# STM32G4_microcontroller.net
KiCad netlist of a schematic drawn in Altium Designer
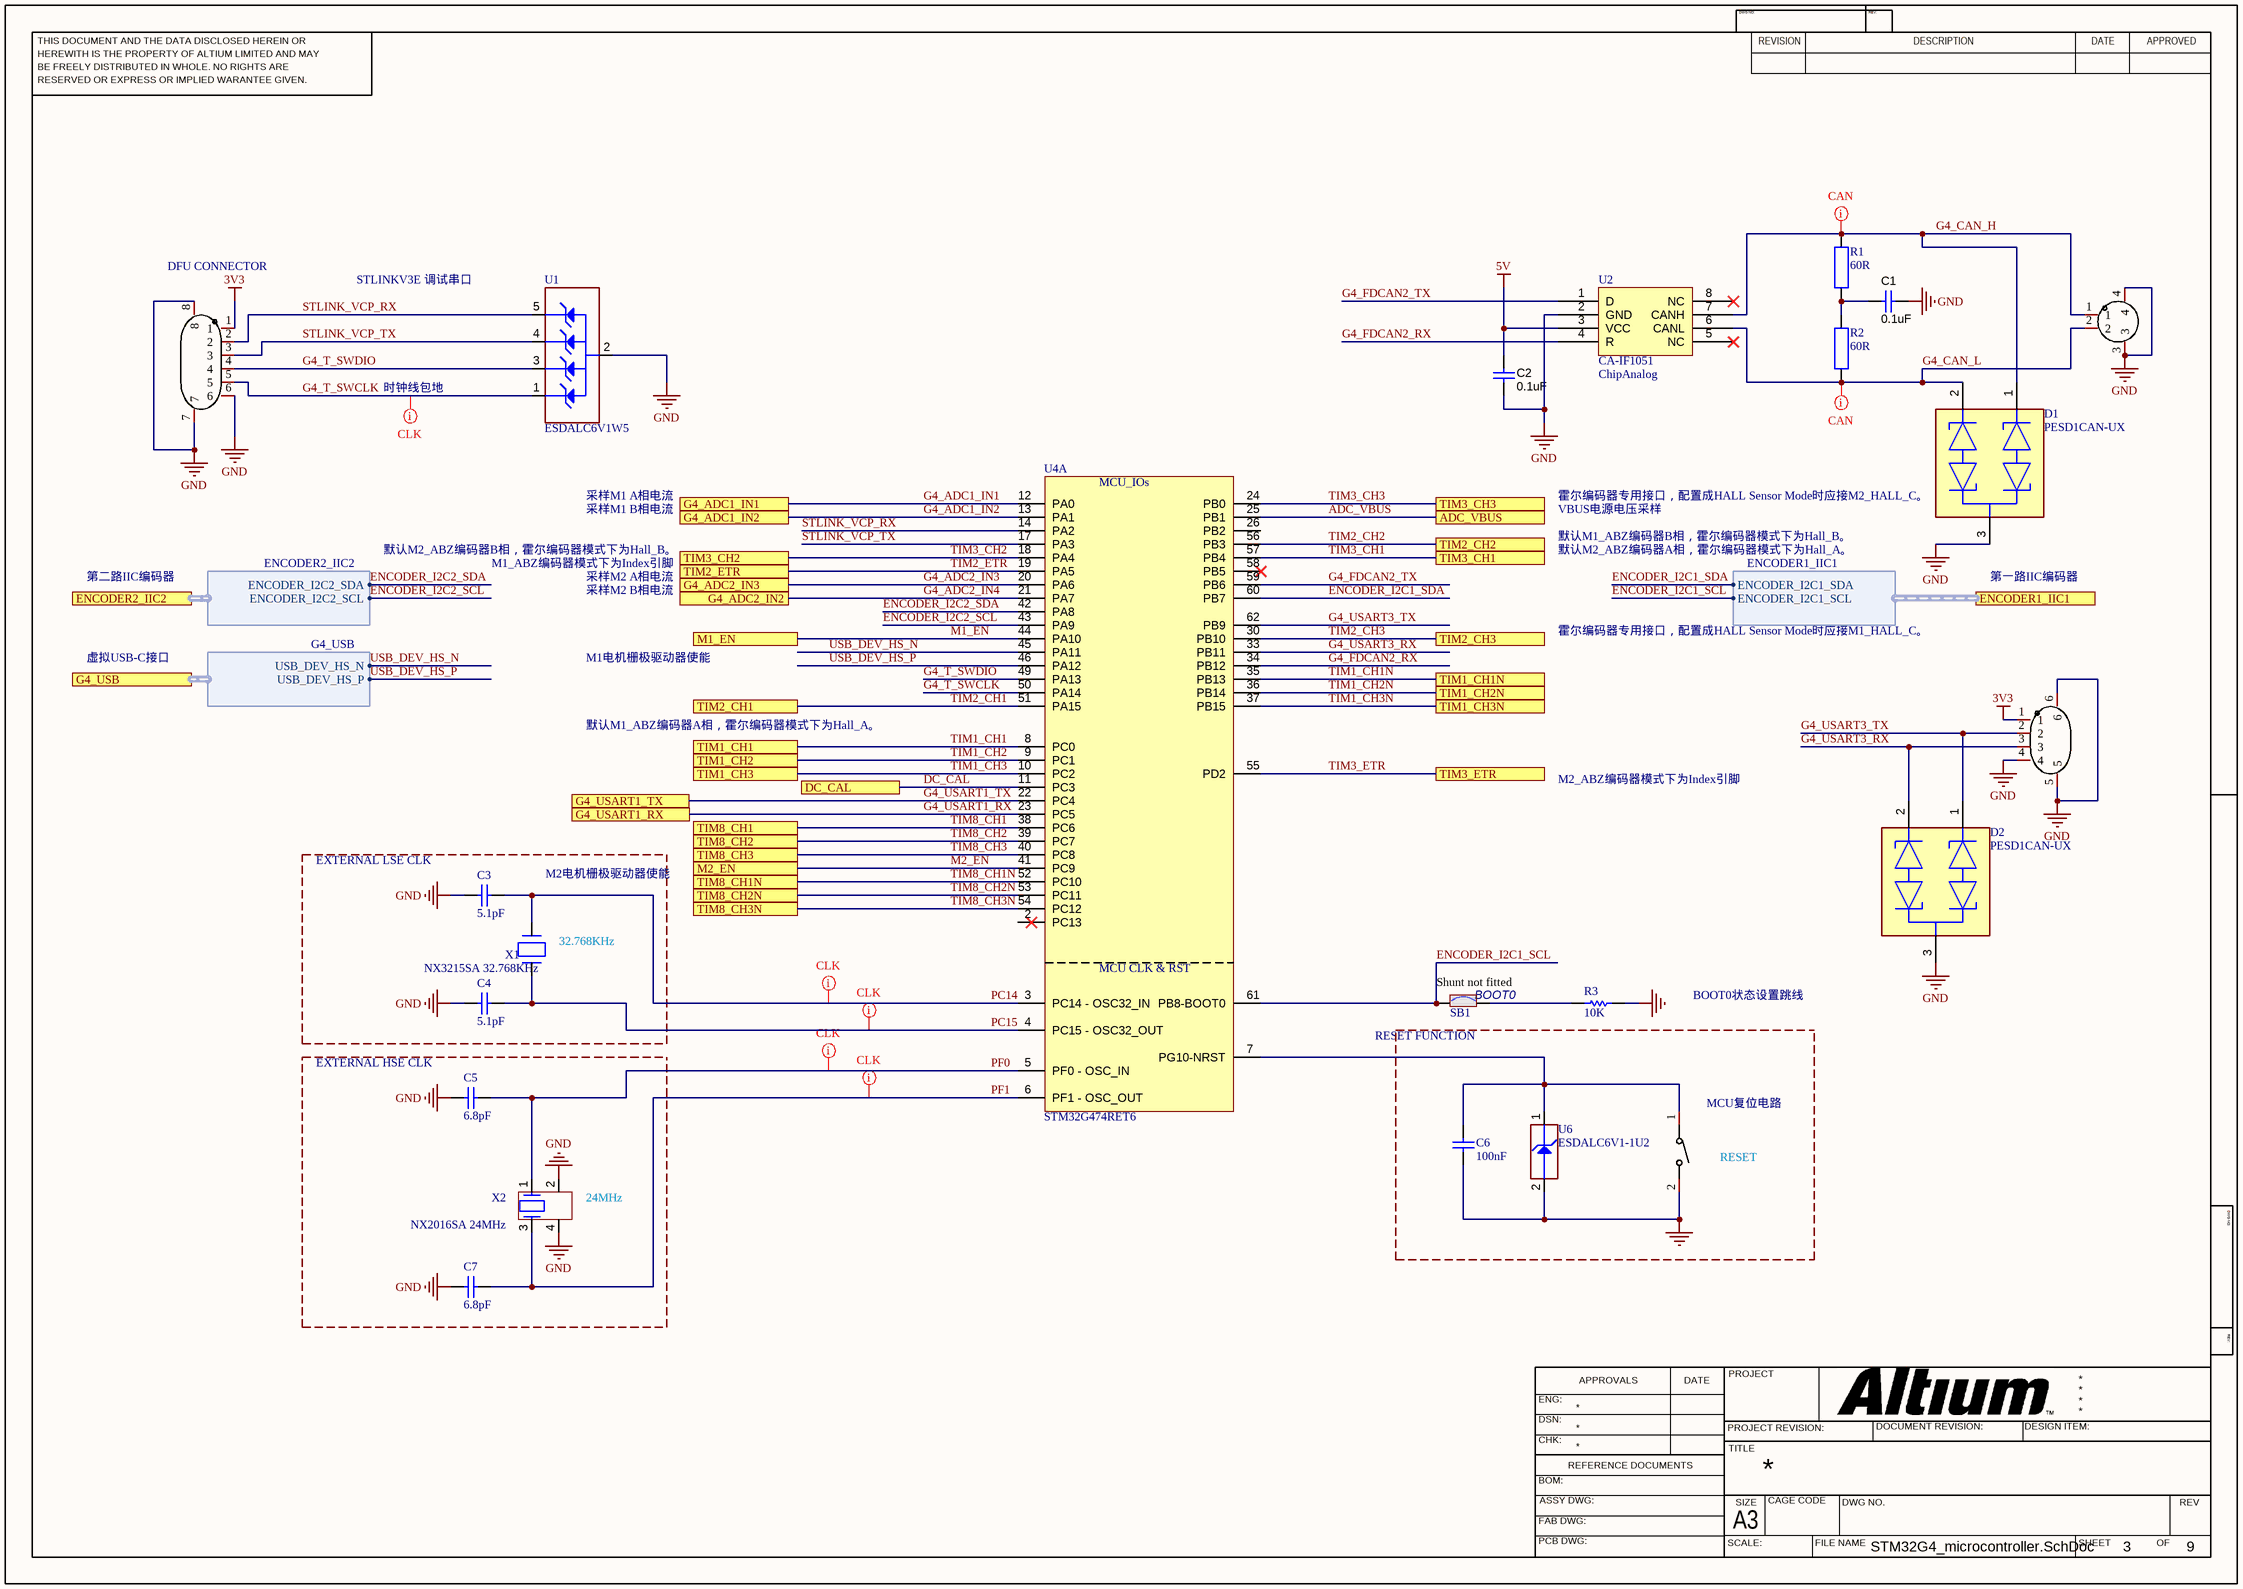
[diagram p0: STM32G4_microcontroller.SchDoc]

(export (version "E")
  (design (tool "Eeschema 10.0.6"))
  (components
    (comp (ref "C1")
      (value "GRM188R61E105KA12D")
      (footprint "0603L")
      (description "CAP, CERM, 0.1uF, 25V, +/-10%, X5R, 0603")
      (fields
        (field (name "VALUEDISPLAYED") "0.1uF")
        (field (name "MANUFACTURER") "MuRata")
        (field (name "PUBLISHER") "Texas Instruments")
      )
      (libsource (lib "Capacitor_Ceramic") (part "GRM188R61E105KA12D"))
    )
    (comp (ref "C2")
      (value "GRM188R61E105KA12D")
      (footprint "0603L")
      (description "CAP, CERM, 0.1uF, 25V, +/-10%, X5R, 0603")
      (fields
        (field (name "VALUEDISPLAYED") "0.1uF")
        (field (name "MANUFACTURER") "MuRata")
        (field (name "PUBLISHER") "Texas Instruments")
      )
      (libsource (lib "Capacitor_Ceramic") (part "GRM188R61E105KA12D"))
    )
    (comp (ref "C3")
      (value "5.1pF")
      (footprint "C0402")
      (description "Capacitor, MLCC, 5.1pF, 50V, NPO, +-0.25pF, 0402, T=0.5mm")
      (fields
        (field (name "INTERNAL_PART_NUMBER") "MCD-00003")
        (field (name "MANUFACTURER_PART_NUMBER") "CC0402CRNPO9BN5R1")
        (field (name "PROVIDED_BY") "SUBCO")
      )
      (libsource (lib "MCD_PARTS_database") (part "Capacitor"))
    )
    (comp (ref "C4")
      (value "5.1pF")
      (footprint "C0402")
      (description "Capacitor, MLCC, 5.1pF, 50V, NPO, +-0.25pF, 0402, T=0.5mm")
      (fields
        (field (name "INTERNAL_PART_NUMBER") "MCD-00003")
        (field (name "MANUFACTURER_PART_NUMBER") "CC0402CRNPO9BN5R1")
        (field (name "PROVIDED_BY") "SUBCO")
      )
      (libsource (lib "MCD_PARTS_database") (part "Capacitor"))
    )
    (comp (ref "C5")
      (value "6.8pF")
      (footprint "C0402")
      (description "Capacitor, MLCC, 6.8pF, 50V, NPO, +-0.25pF, 0402, T=0.5mm")
      (fields
        (field (name "INTERNAL_PART_NUMBER") "MCD-00674")
        (field (name "MANUFACTURER_PART_NUMBER") "CC0402CRNPO9BN6R8")
        (field (name "PROVIDED_BY") "SUBCO")
      )
      (libsource (lib "MCD_PARTS_database") (part "Capacitor"))
    )
    (comp (ref "C6")
      (value "100nF")
      (footprint "C0402")
      (description "Capacitor, MLCC, 100nF, 16V, X7R, 10%, 0402, T=0,5mm")
      (fields
        (field (name "INTERNAL_PART_NUMBER") "MCD-00102")
        (field (name "MANUFACTURER_PART_NUMBER") "CC0402KRX7R7BB104")
        (field (name "PROVIDED_BY") "Subcon")
      )
      (libsource (lib "MCD_PARTS_database") (part "Capacitor"))
    )
    (comp (ref "C7")
      (value "6.8pF")
      (footprint "C0402")
      (description "Capacitor, MLCC, 6.8pF, 50V, NPO, +-0.25pF, 0402, T=0.5mm")
      (fields
        (field (name "INTERNAL_PART_NUMBER") "MCD-00674")
        (field (name "MANUFACTURER_PART_NUMBER") "CC0402CRNPO9BN6R8")
        (field (name "PROVIDED_BY") "SUBCO")
      )
      (libsource (lib "MCD_PARTS_database") (part "Capacitor"))
    )
    (comp (ref "CN1")
      (value "WAFER-GH1.25-2PWB")
      (footprint "CONN-TH_2P-P1.25_XUNPU_WAFER-GH1.25-2PWB")
      (fields (field (name "MANUFACTURER") "XUNPU(讯普)"))
      (libsource (lib "two_ax_PCB") (part "WAFER-GH1.25-2PWB"))
    )
    (comp (ref "D1")
      (value "PESD1CAN-UX")
      (footprint "FP-SOT323-MFG")
      (description "TVS DIODE 24V 50V SC70-3")
      (libsource (lib "Altium Content Vault") (part "04d57993b6b7b0f5b3c95ba4f97dea0"))
    )
    (comp (ref "D2")
      (value "PESD1CAN-UX")
      (footprint "FP-SOT323-MFG")
      (description "TVS DIODE 24V 50V SC70-3")
      (libsource (lib "Altium Content Vault") (part "04d57993b6b7b0f5b3c95ba4f97dea0"))
    )
    (comp (ref "R1")
      (value "60R")
      (footprint "RESC1608X55N")
      (description "RES SMD 60 OHM 1% 1/10W 0603")
      (fields
        (field (name "MANUFACTURER") "Yageo")
        (field (name "MANUFACTURER PART NUMBER") "RC0603FR-07120RL")
      )
      (libsource (lib "CustomComponents") (part "RC0603FR-07120RL"))
    )
    (comp (ref "R2")
      (value "60R")
      (footprint "RESC1608X55N")
      (description "RES SMD 60 OHM 1% 1/10W 0603")
      (fields
        (field (name "MANUFACTURER") "Yageo")
        (field (name "MANUFACTURER PART NUMBER") "RC0603FR-07120RL")
      )
      (libsource (lib "CustomComponents") (part "RC0603FR-07120RL"))
    )
    (comp (ref "R3")
      (value "10K")
      (footprint "R0603")
      (description "Resistor,10K,0603,1%,1/10W")
      (fields
        (field (name "INTERNAL_PART_NUMBER") "MCD-00220")
        (field (name "MANUFACTURER_PART_NUMBER") "RC0603FR-0710KL")
        (field (name "PROVIDED_BY") "Subcon")
      )
      (libsource (lib "MCD_PARTS_database") (part "Resistor"))
    )
    (comp (ref "SB1")
      (value "MCD-00071")
      (footprint "SOLDER-BRIDGE_R0603-0R")
      (description "Solder Bridge ON")
      (fields
        (field (name "MANUFACTURER_PART_NUMBER") "RC0603JR-070RL")
        (field (name "MANUFACTURER") "YAGEO")
        (field (name "PROVIDED_BY") "SUBCO")
      )
      (libsource (lib "mb1367") (part "MCD-00071"))
    )
    (comp (ref "SW1")
      (value "TS-1088-AR02016")
      (footprint "SW-SMD_L3.9-W3.0-P4.45")
      (fields (field (name "MANUFACTURER") "XUNPU(讯普)"))
      (libsource (lib "mb1367") (part "TS-1088-AR02016"))
    )
    (comp (ref "U1")
      (value "ESDALC6V1W5")
      (footprint "ESD_SOT323-5L")
      (description "Dual Transil array for ESD protection")
      (fields
        (field (name "INTERNAL_PART_NUMBER") "MCD-00136")
        (field (name "MANUFACTURER") "STMICROELECTRONICS")
        (field (name "PROVIDED_BY") "Subcon")
      )
      (libsource (lib "MCD_PARTS_database") (part "ESDALC6V1W5"))
    )
    (comp (ref "U2")
      (value "CA-IF1051")
      (footprint "SOIC127P600X175-8N")
      (fields
        (field (name "MANUFACTURER") "Texas Instruments")
        (field (name "MANUFACTURER PART NUMBER") "CA-IF1051")
      )
      (libsource (lib "CustomComponents") (part "SN65HVD232D"))
    )
    (comp (ref "U3")
      (value "WAFER-GH1.25-6PWB")
      (footprint "CONN-SMD_6P-P1.25_XUNPU_WAFER-GH1.25-6PWB")
      (fields (field (name "MANUFACTURER") "XUNPU(讯普)"))
      (libsource (lib "two_ax_PCB") (part "WAFER-GH1.25-6PWB"))
    )
    (comp (ref "U4")
      (value "STM32G474RET6")
      (footprint "ICC_LQFP64_10X10_P050_SOCKET_YAMAICHI_IC149-064-069-B5_NM")
      (description "STM32G474, LQFP64 package,  3D IC footprint with 2D socket footprint.")
      (fields
        (field (name "INTERNAL_PART_NUMBER") "MCD-01243")
        (field (name "MANUFACTURER") "STMICROELECTRONICS")
        (field (name "PROVIDED_BY") "SUBCO with ST control")
      )
      (libsource (lib "MCD_PARTS_database") (part "STM32G4xx_LQFP64"))
    )
    (comp (ref "U5")
      (value "WAFER-GH1.25-4PWB")
      (footprint "CONN-SMD_4P-P1.25_XUNPU_WAFER-GH1.25-4PWB")
      (fields (field (name "MANUFACTURER") "XUNPU(讯普)"))
      (libsource (lib "two_ax_PCB") (part "WAFER-GH1.25-4PWB"))
    )
    (comp (ref "U6")
      (value "ESDALC6V1-1U2")
      (footprint "ESD_ST0201")
      (description "ESD protection 6V1")
      (fields
        (field (name "INTERNAL_PART_NUMBER") "MCD-00170")
        (field (name "MANUFACTURER") "STMICROELECTRONICS")
        (field (name "PROVIDED_BY") "Subcon")
      )
      (libsource (lib "MCD_PARTS_database") (part "ESD-TRANSIL"))
    )
    (comp (ref "X1")
      (value "NX3215SA 32.768KHz")
      (footprint "CRY_NX3215SA_2P")
      (description "Crystal 32.768kHz, 6pF, +-20ppm, 50Kohms max, SMD")
      (fields
        (field (name "INTERNAL_PART_NUMBER") "MCD-00091")
        (field (name "MANUFACTURER_PART_NUMBER") "NX3215SA 32.768KHz EXS00A-MU00525")
        (field (name "PROVIDED_BY") "SUBCO")
      )
      (libsource (lib "MCD_PARTS_database") (part "XTAL_2_PINS"))
    )
    (comp (ref "X2")
      (value "NX2016SA 24MHz")
      (footprint "CRY_NX2016SA_4P")
      (description "Crystal 24MHz, 6pF, +-20ppm, 80ohms max, SMD")
      (fields
        (field (name "INTERNAL_PART_NUMBER") "MCD-01036")
        (field (name "MANUFACTURER_PART_NUMBER") "NX2016SA 24MHz EXS00A-CS10820")
        (field (name "PROVIDED_BY") "SUBCO")
      )
      (libsource (lib "MCD_PARTS_database") (part "XTAL_4_PINS"))
    )
  )
  (nets
    (net (code "4") (name "/ADC_VBUS") (class "Default")
      (node (ref "U4") (pin "25") (pinfunction "PB1_25") (pintype "passive"))
    )
    (net (code "5") (name "/DC_CAL") (class "Default")
      (node (ref "U4") (pin "11") (pinfunction "PC3_11") (pintype "passive"))
    )
    (net (code "6") (name "/ENCODER_I2C1_SCL") (class "Default")
      (node (ref "SB1") (pin "1") (pinfunction "1_1") (pintype "passive"))
      (node (ref "U4") (pin "61") (pinfunction "PB8-BOOT0_61") (pintype "passive"))
    )
    (net (code "7") (name "/ENCODER_I2C1_SDA") (class "Default")
      (node (ref "U4") (pin "60") (pinfunction "PB7_60") (pintype "passive"))
    )
    (net (code "8") (name "/ENCODER_I2C2_SCL") (class "Default")
      (node (ref "U4") (pin "43") (pinfunction "PA9_43") (pintype "passive"))
    )
    (net (code "9") (name "/ENCODER_I2C2_SDA") (class "Default")
      (node (ref "U4") (pin "42") (pinfunction "PA8_42") (pintype "passive"))
    )
    (net (code "10") (name "/G4_ADC1_IN1") (class "Default")
      (node (ref "U4") (pin "12") (pinfunction "PA0_12") (pintype "passive"))
    )
    (net (code "11") (name "/G4_ADC1_IN2") (class "Default")
      (node (ref "U4") (pin "13") (pinfunction "PA1_13") (pintype "passive"))
    )
    (net (code "12") (name "/G4_ADC2_IN3") (class "Default")
      (node (ref "U4") (pin "20") (pinfunction "PA6_20") (pintype "passive"))
    )
    (net (code "13") (name "/G4_ADC2_IN4") (class "Default")
      (node (ref "U4") (pin "21") (pinfunction "PA7_21") (pintype "passive"))
    )
    (net (code "14") (name "/G4_CAN_H") (class "Default")
      (node (ref "CN1") (pin "1") (pinfunction "1_1") (pintype "passive"))
      (node (ref "D1") (pin "1") (pinfunction "cathode_1_1") (pintype "passive"))
      (node (ref "R1") (pin "2") (pinfunction "0_2") (pintype "passive"))
      (node (ref "U2") (pin "7") (pinfunction "CANH_7") (pintype "passive"))
    )
    (net (code "15") (name "/G4_CAN_L") (class "Default")
      (node (ref "CN1") (pin "2") (pinfunction "2_2") (pintype "passive"))
      (node (ref "D1") (pin "2") (pinfunction "cathode_2_2") (pintype "passive"))
      (node (ref "R2") (pin "1") (pinfunction "0_1") (pintype "passive"))
      (node (ref "U2") (pin "6") (pinfunction "CANL_6") (pintype "passive"))
    )
    (net (code "16") (name "/G4_FDCAN2_RX") (class "Default")
      (node (ref "U2") (pin "4") (pinfunction "R_4") (pintype "passive"))
      (node (ref "U4") (pin "34") (pinfunction "PB12_34") (pintype "passive"))
    )
    (net (code "17") (name "/G4_FDCAN2_TX") (class "Default")
      (node (ref "U2") (pin "1") (pinfunction "D_1") (pintype "passive"))
      (node (ref "U4") (pin "59") (pinfunction "PB6_59") (pintype "passive"))
    )
    (net (code "18") (name "/G4_T_SWCLK") (class "Default")
      (node (ref "U1") (pin "1") (pinfunction "IO1_1") (pintype "passive"))
      (node (ref "U3") (pin "5") (pinfunction "5_5") (pintype "passive"))
      (node (ref "U4") (pin "50") (pinfunction "PA14_50") (pintype "passive"))
    )
    (net (code "19") (name "/G4_T_SWDIO") (class "Default")
      (node (ref "U1") (pin "3") (pinfunction "IO2_3") (pintype "passive"))
      (node (ref "U3") (pin "4") (pinfunction "4_4") (pintype "passive"))
      (node (ref "U4") (pin "49") (pinfunction "PA13_49") (pintype "passive"))
    )
    (net (code "20") (name "/G4_USART1_RX") (class "Default")
      (node (ref "U4") (pin "23") (pinfunction "PC5_23") (pintype "passive"))
    )
    (net (code "21") (name "/G4_USART1_TX") (class "Default")
      (node (ref "U4") (pin "22") (pinfunction "PC4_22") (pintype "passive"))
    )
    (net (code "22") (name "/G4_USART3_RX") (class "Default")
      (node (ref "D2") (pin "2") (pinfunction "cathode_2_2") (pintype "passive"))
      (node (ref "U4") (pin "33") (pinfunction "PB11_33") (pintype "passive"))
      (node (ref "U5") (pin "3") (pinfunction "3_3") (pintype "passive"))
    )
    (net (code "23") (name "/G4_USART3_TX") (class "Default")
      (node (ref "D2") (pin "1") (pinfunction "cathode_1_1") (pintype "passive"))
      (node (ref "U4") (pin "62") (pinfunction "PB9_62") (pintype "passive"))
      (node (ref "U5") (pin "2") (pinfunction "2_2") (pintype "passive"))
    )
    (net (code "24") (name "/M1_EN") (class "Default")
      (node (ref "U4") (pin "44") (pinfunction "PA10_44") (pintype "passive"))
    )
    (net (code "25") (name "/M2_EN") (class "Default")
      (node (ref "U4") (pin "41") (pinfunction "PC9_41") (pintype "passive"))
    )
    (net (code "26") (name "/PC14") (class "Default")
      (node (ref "C3") (pin "1") (pinfunction "1_1") (pintype "passive"))
      (node (ref "U4") (pin "3") (pinfunction "PC14_-_OSC32_IN_3") (pintype "passive"))
      (node (ref "X1") (pin "2") (pinfunction "X2_2") (pintype "passive"))
    )
    (net (code "27") (name "/PC15") (class "Default")
      (node (ref "C4") (pin "1") (pinfunction "1_1") (pintype "passive"))
      (node (ref "U4") (pin "4") (pinfunction "PC15_-_OSC32_OUT_4") (pintype "passive"))
      (node (ref "X1") (pin "1") (pinfunction "X1_1") (pintype "passive"))
    )
    (net (code "28") (name "/PF0") (class "Default")
      (node (ref "C5") (pin "2") (pinfunction "2_2") (pintype "passive"))
      (node (ref "U4") (pin "5") (pinfunction "PF0_-_OSC_IN_5") (pintype "passive"))
      (node (ref "X2") (pin "1") (pinfunction "1_1") (pintype "passive"))
    )
    (net (code "29") (name "/PF1") (class "Default")
      (node (ref "C7") (pin "2") (pinfunction "2_2") (pintype "passive"))
      (node (ref "U4") (pin "6") (pinfunction "PF1_-_OSC_OUT_6") (pintype "passive"))
      (node (ref "X2") (pin "3") (pinfunction "3_3") (pintype "passive"))
    )
    (net (code "30") (name "/STLINK_VCP_RX") (class "Default")
      (node (ref "U1") (pin "5") (pinfunction "IO4_5") (pintype "passive"))
      (node (ref "U3") (pin "2") (pinfunction "2_2") (pintype "passive"))
      (node (ref "U4") (pin "14") (pinfunction "PA2_14") (pintype "passive"))
    )
    (net (code "31") (name "/STLINK_VCP_TX") (class "Default")
      (node (ref "U1") (pin "4") (pinfunction "IO3_4") (pintype "passive"))
      (node (ref "U3") (pin "3") (pinfunction "3_3") (pintype "passive"))
      (node (ref "U4") (pin "17") (pinfunction "PA3_17") (pintype "passive"))
    )
    (net (code "32") (name "/TIM1_CH1") (class "Default")
      (node (ref "U4") (pin "8") (pinfunction "PC0_8") (pintype "passive"))
    )
    (net (code "33") (name "/TIM1_CH1N") (class "Default")
      (node (ref "U4") (pin "35") (pinfunction "PB13_35") (pintype "passive"))
    )
    (net (code "34") (name "/TIM1_CH2") (class "Default")
      (node (ref "U4") (pin "9") (pinfunction "PC1_9") (pintype "passive"))
    )
    (net (code "35") (name "/TIM1_CH2N") (class "Default")
      (node (ref "U4") (pin "36") (pinfunction "PB14_36") (pintype "passive"))
    )
    (net (code "36") (name "/TIM1_CH3") (class "Default")
      (node (ref "U4") (pin "10") (pinfunction "PC2_10") (pintype "passive"))
    )
    (net (code "37") (name "/TIM1_CH3N") (class "Default")
      (node (ref "U4") (pin "37") (pinfunction "PB15_37") (pintype "passive"))
    )
    (net (code "38") (name "/TIM2_CH1") (class "Default")
      (node (ref "U4") (pin "51") (pinfunction "PA15_51") (pintype "passive"))
    )
    (net (code "39") (name "/TIM2_CH2") (class "Default")
      (node (ref "U4") (pin "56") (pinfunction "PB3_56") (pintype "passive"))
    )
    (net (code "40") (name "/TIM2_CH3") (class "Default")
      (node (ref "U4") (pin "30") (pinfunction "PB10_30") (pintype "passive"))
    )
    (net (code "41") (name "/TIM2_ETR") (class "Default")
      (node (ref "U4") (pin "19") (pinfunction "PA5_19") (pintype "passive"))
    )
    (net (code "42") (name "/TIM3_CH1") (class "Default")
      (node (ref "U4") (pin "57") (pinfunction "PB4_57") (pintype "passive"))
    )
    (net (code "43") (name "/TIM3_CH2") (class "Default")
      (node (ref "U4") (pin "18") (pinfunction "PA4_18") (pintype "passive"))
    )
    (net (code "44") (name "/TIM3_CH3") (class "Default")
      (node (ref "U4") (pin "24") (pinfunction "PB0_24") (pintype "passive"))
    )
    (net (code "45") (name "/TIM3_ETR") (class "Default")
      (node (ref "U4") (pin "55") (pinfunction "PD2_55") (pintype "passive"))
    )
    (net (code "46") (name "/TIM8_CH1") (class "Default")
      (node (ref "U4") (pin "38") (pinfunction "PC6_38") (pintype "passive"))
    )
    (net (code "47") (name "/TIM8_CH1N") (class "Default")
      (node (ref "U4") (pin "52") (pinfunction "PC10_52") (pintype "passive"))
    )
    (net (code "48") (name "/TIM8_CH2") (class "Default")
      (node (ref "U4") (pin "39") (pinfunction "PC7_39") (pintype "passive"))
    )
    (net (code "49") (name "/TIM8_CH2N") (class "Default")
      (node (ref "U4") (pin "53") (pinfunction "PC11_53") (pintype "passive"))
    )
    (net (code "50") (name "/TIM8_CH3") (class "Default")
      (node (ref "U4") (pin "40") (pinfunction "PC8_40") (pintype "passive"))
    )
    (net (code "51") (name "/TIM8_CH3N") (class "Default")
      (node (ref "U4") (pin "54") (pinfunction "PC12_54") (pintype "passive"))
    )
    (net (code "52") (name "/USB_DEV_HS_N") (class "Default")
      (node (ref "U4") (pin "45") (pinfunction "PA11_45") (pintype "passive"))
    )
    (net (code "53") (name "/USB_DEV_HS_P") (class "Default")
      (node (ref "U4") (pin "46") (pinfunction "PA12_46") (pintype "passive"))
    )
    (net (code "57") (name "3V3") (class "Default")
      (node (ref "U3") (pin "1") (pinfunction "1_1") (pintype "passive"))
      (node (ref "U5") (pin "1") (pinfunction "1_1") (pintype "passive"))
    )
    (net (code "58") (name "5V") (class "Default")
      (node (ref "C2") (pin "1") (pinfunction "1_1") (pintype "passive"))
      (node (ref "U2") (pin "3") (pinfunction "VCC_3") (pintype "passive"))
    )
    (net (code "59") (name "GND") (class "Default")
      (node (ref "C1") (pin "2") (pinfunction "2_2") (pintype "passive"))
      (node (ref "C2") (pin "2") (pinfunction "2_2") (pintype "passive"))
      (node (ref "C3") (pin "2") (pinfunction "2_2") (pintype "passive"))
      (node (ref "C4") (pin "2") (pinfunction "2_2") (pintype "passive"))
      (node (ref "C5") (pin "1") (pinfunction "1_1") (pintype "passive"))
      (node (ref "C6") (pin "1") (pinfunction "1_1") (pintype "passive"))
      (node (ref "C7") (pin "1") (pinfunction "1_1") (pintype "passive"))
      (node (ref "CN1") (pin "3") (pinfunction "3_3") (pintype "passive"))
      (node (ref "CN1") (pin "4") (pinfunction "4_4") (pintype "passive"))
      (node (ref "D1") (pin "3") (pinfunction "common_cathode_3") (pintype "passive"))
      (node (ref "D2") (pin "3") (pinfunction "common_cathode_3") (pintype "passive"))
      (node (ref "R3") (pin "1") (pinfunction "1_1") (pintype "passive"))
      (node (ref "SW1") (pin "2") (pinfunction "2_2") (pintype "passive"))
      (node (ref "U1") (pin "2") (pinfunction "GND_2") (pintype "passive"))
      (node (ref "U2") (pin "2") (pinfunction "GND_2") (pintype "passive"))
      (node (ref "U3") (pin "6") (pinfunction "6_6") (pintype "passive"))
      (node (ref "U3") (pin "7") (pinfunction "7_7") (pintype "passive"))
      (node (ref "U3") (pin "8") (pinfunction "8_8") (pintype "passive"))
      (node (ref "U5") (pin "4") (pinfunction "4_4") (pintype "passive"))
      (node (ref "U5") (pin "5") (pinfunction "5_5") (pintype "passive"))
      (node (ref "U5") (pin "6") (pinfunction "6_6") (pintype "passive"))
      (node (ref "U6") (pin "2") (pinfunction "GND_2") (pintype "passive"))
      (node (ref "X2") (pin "2") (pinfunction "2_2") (pintype "passive"))
      (node (ref "X2") (pin "4") (pinfunction "4_4") (pintype "passive"))
    )
    (net (code "60") (name "Net-(C1-Pad1)") (class "Default")
      (node (ref "C1") (pin "1") (pinfunction "1_1") (pintype "passive"))
      (node (ref "R1") (pin "1") (pinfunction "0_1") (pintype "passive"))
      (node (ref "R2") (pin "2") (pinfunction "0_2") (pintype "passive"))
    )
    (net (code "61") (name "Net-(R3-Pad2)") (class "Default")
      (node (ref "R3") (pin "2") (pinfunction "2_2") (pintype "passive"))
      (node (ref "SB1") (pin "2") (pinfunction "2_2") (pintype "passive"))
    )
    (net (code "62") (name "Net-(U4A-PG10-NRST)") (class "Default")
      (node (ref "C6") (pin "2") (pinfunction "2_2") (pintype "passive"))
      (node (ref "SW1") (pin "1") (pinfunction "1_1") (pintype "passive"))
      (node (ref "U4") (pin "7") (pinfunction "PG10-NRST_7") (pintype "passive"))
      (node (ref "U6") (pin "1") (pinfunction "IO1_1") (pintype "passive"))
    )
    (net (code "63") (name "unconnected-(U2-NC-Pad5)") (class "Default")
      (node (ref "U2") (pin "5") (pinfunction "NC_5") (pintype "passive+no_connect"))
    )
    (net (code "64") (name "unconnected-(U2-NC-Pad8)") (class "Default")
      (node (ref "U2") (pin "8") (pinfunction "NC_8") (pintype "passive+no_connect"))
    )
    (net (code "65") (name "unconnected-(U4A-PB2-Pad26)") (class "Default")
      (node (ref "U4") (pin "26") (pinfunction "PB2_26") (pintype "passive"))
    )
    (net (code "66") (name "unconnected-(U4A-PB5-Pad58)") (class "Default")
      (node (ref "U4") (pin "58") (pinfunction "PB5_58") (pintype "passive+no_connect"))
    )
    (net (code "67") (name "unconnected-(U4A-PC13-Pad2)") (class "Default")
      (node (ref "U4") (pin "2") (pinfunction "PC13_2") (pintype "passive"))
    )
  )
)
